# ir_board_mount.net
KiCad netlist of a schematic drawn in EAGLE
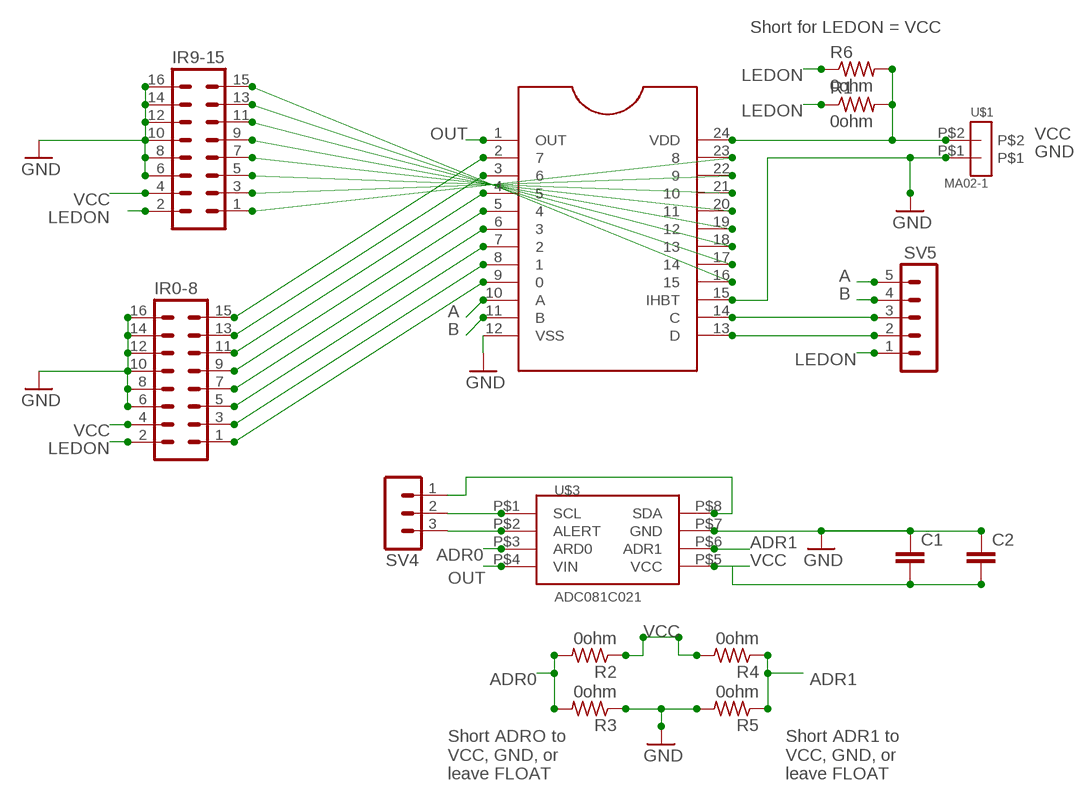
[diagram p0: schematic, sheet 1]

(export (version "E")
  (design (tool "Eeschema 10.0.6"))
  (components
    (comp (ref "C1")
      (value "C-EUC0805K")
      (footprint "eagle-import:C0805K")
      (libsource (lib "eagle-import") (part "C-EUC0805K"))
    )
    (comp (ref "C2")
      (value "C-EUC0805K")
      (footprint "eagle-import:C0805K")
      (libsource (lib "eagle-import") (part "C-EUC0805K"))
    )
    (comp (ref "IR0-8")
      (value "MA08-2")
      (footprint "eagle-import:MA08-2")
      (libsource (lib "eagle-import") (part "MA08-2"))
    )
    (comp (ref "IR9-15")
      (value "MA08-2")
      (footprint "eagle-import:MA08-2")
      (libsource (lib "eagle-import") (part "MA08-2"))
    )
    (comp (ref "R1")
      (value "0ohm")
      (footprint "eagle-import:R0805")
      (libsource (lib "eagle-import") (part "R-US_R0805"))
    )
    (comp (ref "R2")
      (value "0ohm")
      (footprint "eagle-import:R0805")
      (libsource (lib "eagle-import") (part "R-US_R0805"))
    )
    (comp (ref "R3")
      (value "0ohm")
      (footprint "eagle-import:R0805")
      (libsource (lib "eagle-import") (part "R-US_R0805"))
    )
    (comp (ref "R4")
      (value "0ohm")
      (footprint "eagle-import:R0805")
      (libsource (lib "eagle-import") (part "R-US_R0805"))
    )
    (comp (ref "R5")
      (value "0ohm")
      (footprint "eagle-import:R0805")
      (libsource (lib "eagle-import") (part "R-US_R0805"))
    )
    (comp (ref "R6")
      (value "0ohm")
      (footprint "eagle-import:R0805")
      (libsource (lib "eagle-import") (part "R-US_R0805"))
    )
    (comp (ref "SV4")
      (value "MA03-1")
      (footprint "eagle-import:MA03-1")
      (libsource (lib "eagle-import") (part "MA03-1"))
    )
    (comp (ref "SV5")
      (value "MA05-1")
      (footprint "eagle-import:MA05-1")
      (libsource (lib "eagle-import") (part "MA05-1"))
    )
    (comp (ref "U$1")
      (value "MA02-1")
      (footprint "eagle-import:MA02-1")
      (libsource (lib "eagle-import") (part "MA02-1"))
    )
    (comp (ref "U$2")
      (value "16BIT_ANALOG_MUX")
      (footprint "eagle-import:DIL24-6")
      (libsource (lib "eagle-import") (part "16BIT_ANALOG_MUX"))
    )
    (comp (ref "U$3")
      (value "ADC081C021")
      (footprint "eagle-import:TSSOP-8")
      (libsource (lib "eagle-import") (part "ADC081C021"))
    )
  )
  (nets
    (net (code "1") (name "/A") (class "Default")
      (node (ref "SV5") (pin "5") (pinfunction "5_5") (pintype "passive"))
      (node (ref "U$2") (pin "10") (pinfunction "A_10") (pintype "bidirectional"))
    )
    (net (code "2") (name "/ADR0") (class "Default")
      (node (ref "R2") (pin "2") (pinfunction "2_2") (pintype "passive"))
      (node (ref "R3") (pin "2") (pinfunction "2_2") (pintype "passive"))
      (node (ref "U$3") (pin "P$3") (pinfunction "ARD0_P$3") (pintype "bidirectional"))
    )
    (net (code "3") (name "/ADR1") (class "Default")
      (node (ref "R4") (pin "1") (pinfunction "1_1") (pintype "passive"))
      (node (ref "R5") (pin "1") (pinfunction "1_1") (pintype "passive"))
      (node (ref "U$3") (pin "P$6") (pinfunction "ADR1_P$6") (pintype "bidirectional"))
    )
    (net (code "4") (name "/B") (class "Default")
      (node (ref "SV5") (pin "4") (pinfunction "4_4") (pintype "passive"))
      (node (ref "U$2") (pin "11") (pinfunction "B_11") (pintype "bidirectional"))
    )
    (net (code "5") (name "/LEDON") (class "Default")
      (node (ref "IR0-8") (pin "2") (pinfunction "2_2") (pintype "passive"))
      (node (ref "IR9-15") (pin "2") (pinfunction "2_2") (pintype "passive"))
      (node (ref "R1") (pin "1") (pinfunction "1_1") (pintype "passive"))
      (node (ref "R6") (pin "1") (pinfunction "1_1") (pintype "passive"))
      (node (ref "SV5") (pin "1") (pinfunction "1_1") (pintype "passive"))
    )
    (net (code "6") (name "/OUT") (class "Default")
      (node (ref "U$2") (pin "1") (pinfunction "OUT_1") (pintype "bidirectional"))
      (node (ref "U$3") (pin "P$4") (pinfunction "VIN_P$4") (pintype "bidirectional"))
    )
    (net (code "7") (name "/VCC") (class "Default")
      (node (ref "C1") (pin "2") (pinfunction "2_2") (pintype "passive"))
      (node (ref "C2") (pin "2") (pinfunction "2_2") (pintype "passive"))
      (node (ref "IR0-8") (pin "4") (pinfunction "4_4") (pintype "passive"))
      (node (ref "IR9-15") (pin "4") (pinfunction "4_4") (pintype "passive"))
      (node (ref "R1") (pin "2") (pinfunction "2_2") (pintype "passive"))
      (node (ref "R2") (pin "1") (pinfunction "1_1") (pintype "passive"))
      (node (ref "R4") (pin "2") (pinfunction "2_2") (pintype "passive"))
      (node (ref "R6") (pin "2") (pinfunction "2_2") (pintype "passive"))
      (node (ref "U$1") (pin "P$2") (pinfunction "P$2_P$2") (pintype "bidirectional"))
      (node (ref "U$2") (pin "24") (pinfunction "VDD_24") (pintype "bidirectional"))
      (node (ref "U$3") (pin "P$5") (pinfunction "VCC_P$5") (pintype "bidirectional"))
    )
    (net (code "8") (name "GND") (class "Default")
      (node (ref "C1") (pin "1") (pinfunction "1_1") (pintype "passive"))
      (node (ref "C2") (pin "1") (pinfunction "1_1") (pintype "passive"))
      (node (ref "IR0-8") (pin "10") (pinfunction "10_10") (pintype "passive"))
      (node (ref "IR0-8") (pin "12") (pinfunction "12_12") (pintype "passive"))
      (node (ref "IR0-8") (pin "14") (pinfunction "14_14") (pintype "passive"))
      (node (ref "IR0-8") (pin "16") (pinfunction "16_16") (pintype "passive"))
      (node (ref "IR0-8") (pin "6") (pinfunction "6_6") (pintype "passive"))
      (node (ref "IR0-8") (pin "8") (pinfunction "8_8") (pintype "passive"))
      (node (ref "IR9-15") (pin "10") (pinfunction "10_10") (pintype "passive"))
      (node (ref "IR9-15") (pin "12") (pinfunction "12_12") (pintype "passive"))
      (node (ref "IR9-15") (pin "14") (pinfunction "14_14") (pintype "passive"))
      (node (ref "IR9-15") (pin "16") (pinfunction "16_16") (pintype "passive"))
      (node (ref "IR9-15") (pin "6") (pinfunction "6_6") (pintype "passive"))
      (node (ref "IR9-15") (pin "8") (pinfunction "8_8") (pintype "passive"))
      (node (ref "R3") (pin "1") (pinfunction "1_1") (pintype "passive"))
      (node (ref "R5") (pin "2") (pinfunction "2_2") (pintype "passive"))
      (node (ref "U$1") (pin "P$1") (pinfunction "P$1_P$1") (pintype "bidirectional"))
      (node (ref "U$2") (pin "12") (pinfunction "VSS_12") (pintype "bidirectional"))
      (node (ref "U$2") (pin "15") (pinfunction "IHBT_15") (pintype "bidirectional"))
      (node (ref "U$3") (pin "P$7") (pinfunction "GND_P$7") (pintype "bidirectional"))
    )
    (net (code "9") (name "Net-(U$2-0)") (class "Default")
      (node (ref "IR0-8") (pin "1") (pinfunction "1_1") (pintype "passive"))
      (node (ref "U$2") (pin "9") (pinfunction "0_9") (pintype "bidirectional"))
    )
    (net (code "10") (name "Net-(U$2-1)") (class "Default")
      (node (ref "IR0-8") (pin "3") (pinfunction "3_3") (pintype "passive"))
      (node (ref "U$2") (pin "8") (pinfunction "1_8") (pintype "bidirectional"))
    )
    (net (code "11") (name "Net-(U$2-2)") (class "Default")
      (node (ref "IR0-8") (pin "5") (pinfunction "5_5") (pintype "passive"))
      (node (ref "U$2") (pin "7") (pinfunction "2_7") (pintype "bidirectional"))
    )
    (net (code "12") (name "Net-(U$2-3)") (class "Default")
      (node (ref "IR0-8") (pin "7") (pinfunction "7_7") (pintype "passive"))
      (node (ref "U$2") (pin "6") (pinfunction "3_6") (pintype "bidirectional"))
    )
    (net (code "13") (name "Net-(U$2-4)") (class "Default")
      (node (ref "IR0-8") (pin "9") (pinfunction "9_9") (pintype "passive"))
      (node (ref "U$2") (pin "5") (pinfunction "4_5") (pintype "bidirectional"))
    )
    (net (code "14") (name "Net-(U$2-5)") (class "Default")
      (node (ref "IR0-8") (pin "11") (pinfunction "11_11") (pintype "passive"))
      (node (ref "U$2") (pin "4") (pinfunction "5_4") (pintype "bidirectional"))
    )
    (net (code "15") (name "Net-(U$2-6)") (class "Default")
      (node (ref "IR0-8") (pin "13") (pinfunction "13_13") (pintype "passive"))
      (node (ref "U$2") (pin "3") (pinfunction "6_3") (pintype "bidirectional"))
    )
    (net (code "16") (name "Net-(U$2-7)") (class "Default")
      (node (ref "IR0-8") (pin "15") (pinfunction "15_15") (pintype "passive"))
      (node (ref "U$2") (pin "2") (pinfunction "7_2") (pintype "bidirectional"))
    )
    (net (code "17") (name "Net-(U$2-8)") (class "Default")
      (node (ref "IR9-15") (pin "1") (pinfunction "1_1") (pintype "passive"))
      (node (ref "U$2") (pin "23") (pinfunction "8_23") (pintype "bidirectional"))
    )
    (net (code "18") (name "Net-(U$2-9)") (class "Default")
      (node (ref "IR9-15") (pin "3") (pinfunction "3_3") (pintype "passive"))
      (node (ref "U$2") (pin "22") (pinfunction "9_22") (pintype "bidirectional"))
    )
    (net (code "19") (name "Net-(U$2-10)") (class "Default")
      (node (ref "IR9-15") (pin "5") (pinfunction "5_5") (pintype "passive"))
      (node (ref "U$2") (pin "21") (pinfunction "10_21") (pintype "bidirectional"))
    )
    (net (code "20") (name "Net-(U$2-11)") (class "Default")
      (node (ref "IR9-15") (pin "7") (pinfunction "7_7") (pintype "passive"))
      (node (ref "U$2") (pin "20") (pinfunction "11_20") (pintype "bidirectional"))
    )
    (net (code "21") (name "Net-(U$2-12)") (class "Default")
      (node (ref "IR9-15") (pin "9") (pinfunction "9_9") (pintype "passive"))
      (node (ref "U$2") (pin "19") (pinfunction "12_19") (pintype "bidirectional"))
    )
    (net (code "22") (name "Net-(U$2-13)") (class "Default")
      (node (ref "IR9-15") (pin "11") (pinfunction "11_11") (pintype "passive"))
      (node (ref "U$2") (pin "18") (pinfunction "13_18") (pintype "bidirectional"))
    )
    (net (code "23") (name "Net-(U$2-14)") (class "Default")
      (node (ref "IR9-15") (pin "13") (pinfunction "13_13") (pintype "passive"))
      (node (ref "U$2") (pin "17") (pinfunction "14_17") (pintype "bidirectional"))
    )
    (net (code "24") (name "Net-(U$2-15)") (class "Default")
      (node (ref "IR9-15") (pin "15") (pinfunction "15_15") (pintype "passive"))
      (node (ref "U$2") (pin "16") (pinfunction "15_16") (pintype "bidirectional"))
    )
    (net (code "25") (name "Net-(U$2-C)") (class "Default")
      (node (ref "SV5") (pin "3") (pinfunction "3_3") (pintype "passive"))
      (node (ref "U$2") (pin "14") (pinfunction "C_14") (pintype "bidirectional"))
    )
    (net (code "26") (name "Net-(U$2-D)") (class "Default")
      (node (ref "SV5") (pin "2") (pinfunction "2_2") (pintype "passive"))
      (node (ref "U$2") (pin "13") (pinfunction "D_13") (pintype "bidirectional"))
    )
    (net (code "27") (name "Net-(U$3-ALERT)") (class "Default")
      (node (ref "SV4") (pin "3") (pinfunction "3_3") (pintype "passive"))
      (node (ref "U$3") (pin "P$2") (pinfunction "ALERT_P$2") (pintype "bidirectional"))
    )
    (net (code "28") (name "Net-(U$3-SCL)") (class "Default")
      (node (ref "SV4") (pin "2") (pinfunction "2_2") (pintype "passive"))
      (node (ref "U$3") (pin "P$1") (pinfunction "SCL_P$1") (pintype "bidirectional"))
    )
    (net (code "29") (name "Net-(U$3-SDA)") (class "Default")
      (node (ref "SV4") (pin "1") (pinfunction "1_1") (pintype "passive"))
      (node (ref "U$3") (pin "P$8") (pinfunction "SDA_P$8") (pintype "bidirectional"))
    )
  )
)
